# Power.net
KiCad netlist of a schematic drawn in Altium Designer
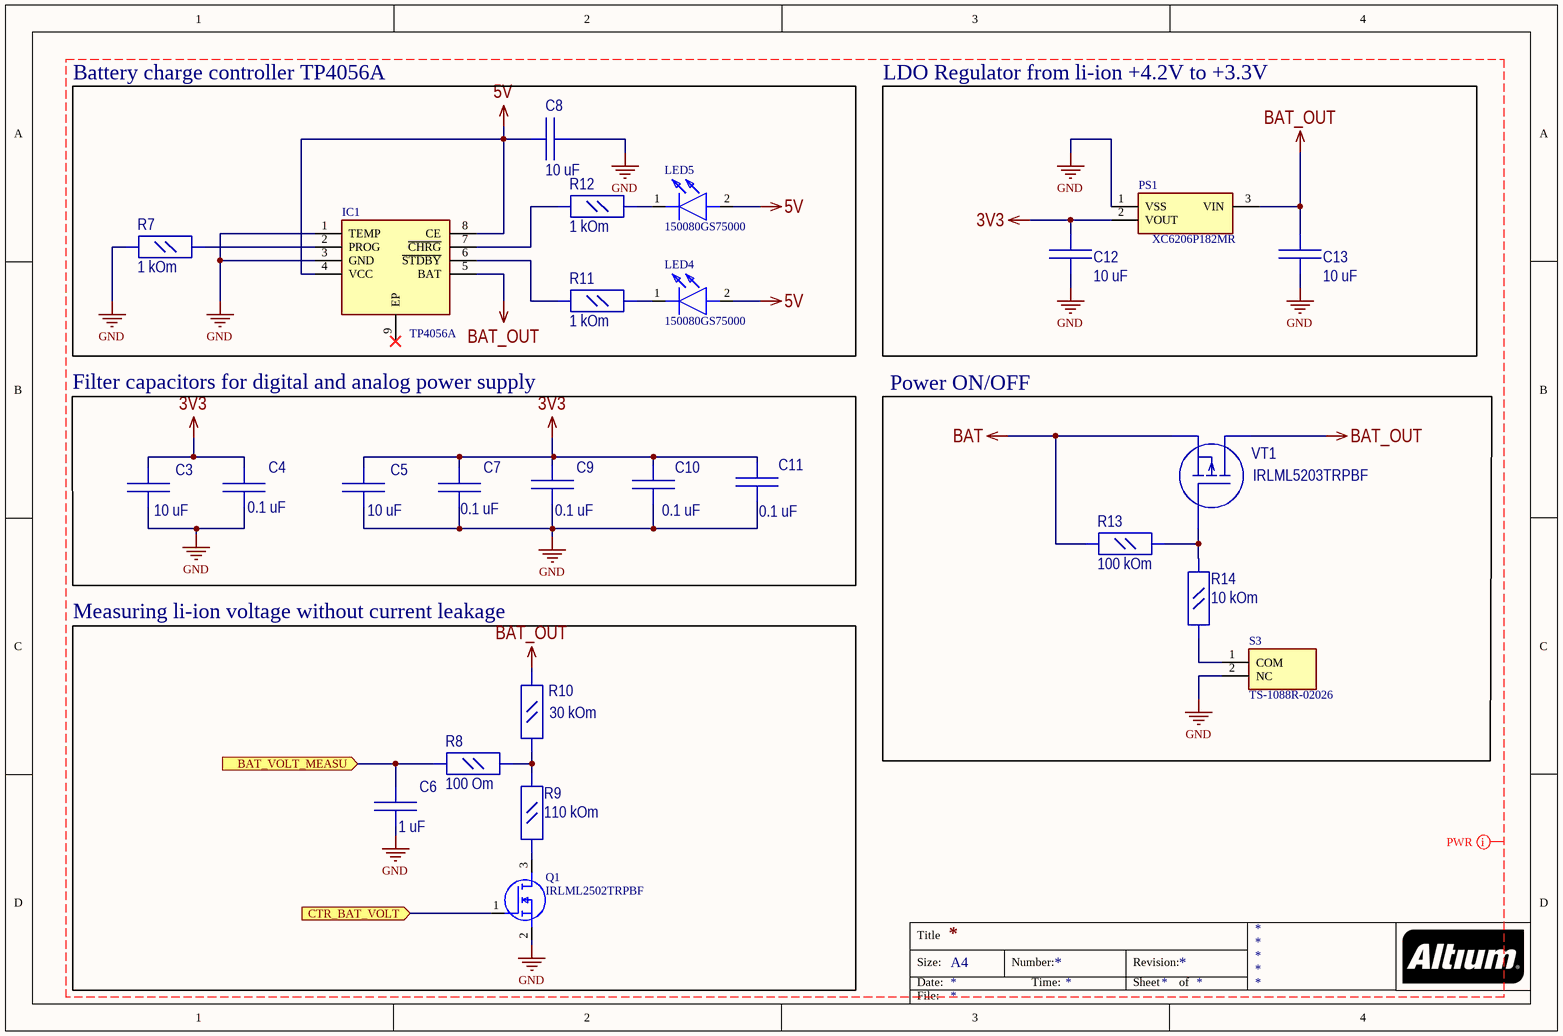
[diagram p0: Power.SchDoc]

(export (version "E")
  (design (tool "Eeschema 10.0.6"))
  (components
    (comp (ref "C3") (value "10 uF") (footprint "C_0805") (libsource (lib "2.Capasitors") (part "C_0805")))
    (comp (ref "C4") (value "0.1 uF") (footprint "C_0805") (libsource (lib "2.Capasitors") (part "C_0805")))
    (comp (ref "C5") (value "10 uF") (footprint "C_0805") (libsource (lib "2.Capasitors") (part "C_0805")))
    (comp (ref "C6") (value "1 uF") (footprint "C_0805") (libsource (lib "2.Capasitors") (part "C_0805")))
    (comp (ref "C7") (value "0.1 uF") (footprint "C_0805") (libsource (lib "2.Capasitors") (part "C_0805")))
    (comp (ref "C8") (value "10 uF") (footprint "C_0805") (libsource (lib "2.Capasitors") (part "C_0805")))
    (comp (ref "C9") (value "0.1 uF") (footprint "C_0805") (libsource (lib "2.Capasitors") (part "C_0805")))
    (comp (ref "C10") (value "0.1 uF") (footprint "C_0805") (libsource (lib "2.Capasitors") (part "C_0805")))
    (comp (ref "C11") (value "0.1 uF") (footprint "C_0805") (libsource (lib "2.Capasitors") (part "C_0805")))
    (comp (ref "C12") (value "10 uF") (footprint "C_0805") (libsource (lib "2.Capasitors") (part "C_0805")))
    (comp (ref "C13") (value "10 uF") (footprint "C_0805") (libsource (lib "2.Capasitors") (part "C_0805")))
    (comp (ref "IC1")
      (value "TP4056A")
      (footprint "SamacSys:SOIC127P600X175-9N")
      (description "Integrated Circuit")
      (libsource (lib "*") (part "TP4056A"))
    )
    (comp (ref "LED4")
      (value "150080GS75000")
      (footprint "SamacSys:LEDM2012X80N")
      (description "LED")
      (fields (field (name "MOUSER PART NUMBER") "710-150080GS75000"))
      (libsource (lib "*") (part "150080GS75000"))
    )
    (comp (ref "LED5")
      (value "150080GS75000")
      (footprint "SamacSys:LEDM2012X80N")
      (description "LED")
      (fields (field (name "MOUSER PART NUMBER") "710-150080GS75000"))
      (libsource (lib "*") (part "150080GS75000"))
    )
    (comp (ref "PS1")
      (value "XC6206P182MR")
      (footprint "SamacSys:SOT95P280X130-3N")
      (description "Power Supply")
      (libsource (lib "*") (part "XC6206P182MR"))
    )
    (comp (ref "Q1")
      (value "IRLML2502TRPBF")
      (footprint "SamacSys:SOT95P237X112-3N")
      (description "MOSFET (N-Channel)")
      (fields (field (name "MOUSER PART NUMBER") "942-IRLML2502TRPBF"))
      (libsource (lib "*") (part "IRLML2502TRPBF"))
    )
    (comp (ref "R7") (value "1 kOm") (footprint "R_0805") (libsource (lib "1.Resistors") (part "R_0805")))
    (comp (ref "R8") (value "100 Om") (footprint "R_0805") (libsource (lib "1.Resistors") (part "R_0805")))
    (comp (ref "R9") (value "110 kOm") (footprint "R_0805") (libsource (lib "1.Resistors") (part "R_0805")))
    (comp (ref "R10") (value "30 kOm") (footprint "R_0805") (libsource (lib "1.Resistors") (part "R_0805")))
    (comp (ref "R11") (value "1 kOm") (footprint "R_0805") (libsource (lib "1.Resistors") (part "R_0805")))
    (comp (ref "R12") (value "1 kOm") (footprint "R_0805") (libsource (lib "1.Resistors") (part "R_0805")))
    (comp (ref "R13") (value "100 kOm") (footprint "R_0805") (libsource (lib "1.Resistors") (part "R_0805")))
    (comp (ref "R14") (value "10 kOm") (footprint "R_0805") (libsource (lib "1.Resistors") (part "R_0805")))
    (comp (ref "S3")
      (value "TS-1088R-02026")
      (footprint "SamacSys:TS1088R02026")
      (description "Switch")
      (libsource (lib "*") (part "TS-1088R-02026"))
    )
    (comp (ref "VT1")
      (value "IRLML5203TRPBF")
      (footprint "SOT23")
      (description "Транзистор, P-канал 30В 3A logic")
      (libsource (lib "5.Transistors") (part "IRLML5203TRPBF"))
    )
  )
  (nets
    (net (code "1") (name "/BAT_VOLT_MEASU") (class "Default")
      (node (ref "C6") (pin "2") (pinfunction "2_2") (pintype "passive"))
      (node (ref "R8") (pin "2") (pinfunction "2_2") (pintype "passive"))
    )
    (net (code "2") (name "/CTR_BAT_VOLT") (class "Default")
      (node (ref "Q1") (pin "1") (pinfunction "G_1") (pintype "passive"))
    )
    (net (code "3") (name "3V3") (class "Default")
      (node (ref "C10") (pin "2") (pinfunction "2_2") (pintype "passive"))
      (node (ref "C11") (pin "2") (pinfunction "2_2") (pintype "passive"))
      (node (ref "C12") (pin "1") (pinfunction "1_1") (pintype "passive"))
      (node (ref "C3") (pin "2") (pinfunction "2_2") (pintype "passive"))
      (node (ref "C4") (pin "2") (pinfunction "2_2") (pintype "passive"))
      (node (ref "C5") (pin "2") (pinfunction "2_2") (pintype "passive"))
      (node (ref "C7") (pin "2") (pinfunction "2_2") (pintype "passive"))
      (node (ref "C9") (pin "2") (pinfunction "2_2") (pintype "passive"))
      (node (ref "PS1") (pin "2") (pinfunction "VOUT_2") (pintype "passive"))
    )
    (net (code "4") (name "5V") (class "Default")
      (node (ref "C8") (pin "2") (pinfunction "2_2") (pintype "passive"))
      (node (ref "IC1") (pin "4") (pinfunction "VCC_4") (pintype "passive"))
      (node (ref "IC1") (pin "8") (pinfunction "CE_8") (pintype "passive"))
      (node (ref "LED4") (pin "2") (pinfunction "A_2") (pintype "passive"))
      (node (ref "LED5") (pin "2") (pinfunction "A_2") (pintype "passive"))
    )
    (net (code "5") (name "BAT") (class "Default")
      (node (ref "R13") (pin "2") (pinfunction "2_2") (pintype "passive"))
      (node (ref "VT1") (pin "2") (pinfunction "S_2") (pintype "passive"))
    )
    (net (code "6") (name "BAT_OUT") (class "Default")
      (node (ref "C13") (pin "1") (pinfunction "1_1") (pintype "passive"))
      (node (ref "IC1") (pin "5") (pinfunction "BAT_5") (pintype "passive"))
      (node (ref "PS1") (pin "3") (pinfunction "VIN_3") (pintype "passive"))
      (node (ref "R10") (pin "2") (pinfunction "2_2") (pintype "passive"))
      (node (ref "VT1") (pin "3") (pinfunction "D_3") (pintype "passive"))
    )
    (net (code "7") (name "GND") (class "Default")
      (node (ref "C10") (pin "1") (pinfunction "1_1") (pintype "passive"))
      (node (ref "C11") (pin "1") (pinfunction "1_1") (pintype "passive"))
      (node (ref "C12") (pin "2") (pinfunction "2_2") (pintype "passive"))
      (node (ref "C13") (pin "2") (pinfunction "2_2") (pintype "passive"))
      (node (ref "C3") (pin "1") (pinfunction "1_1") (pintype "passive"))
      (node (ref "C4") (pin "1") (pinfunction "1_1") (pintype "passive"))
      (node (ref "C5") (pin "1") (pinfunction "1_1") (pintype "passive"))
      (node (ref "C6") (pin "1") (pinfunction "1_1") (pintype "passive"))
      (node (ref "C7") (pin "1") (pinfunction "1_1") (pintype "passive"))
      (node (ref "C8") (pin "1") (pinfunction "1_1") (pintype "passive"))
      (node (ref "C9") (pin "1") (pinfunction "1_1") (pintype "passive"))
      (node (ref "IC1") (pin "1") (pinfunction "TEMP_1") (pintype "passive"))
      (node (ref "IC1") (pin "3") (pinfunction "GND_3") (pintype "passive"))
      (node (ref "PS1") (pin "1") (pinfunction "VSS_1") (pintype "passive"))
      (node (ref "Q1") (pin "2") (pinfunction "S_2") (pintype "passive"))
      (node (ref "R7") (pin "2") (pinfunction "2_2") (pintype "passive"))
      (node (ref "S3") (pin "2") (pinfunction "NC_2") (pintype "passive"))
    )
    (net (code "8") (name "Net-(IC1-PROG)") (class "Default")
      (node (ref "IC1") (pin "2") (pinfunction "PROG_2") (pintype "passive"))
      (node (ref "R7") (pin "1") (pinfunction "1_1") (pintype "passive"))
    )
    (net (code "9") (name "Net-(IC1-~{CHRG})") (class "Default")
      (node (ref "IC1") (pin "7") (pinfunction "~{CHRG}_7") (pintype "passive"))
      (node (ref "R12") (pin "2") (pinfunction "2_2") (pintype "passive"))
    )
    (net (code "10") (name "Net-(IC1-~{STDBY})") (class "Default")
      (node (ref "IC1") (pin "6") (pinfunction "~{STDBY}_6") (pintype "passive"))
      (node (ref "R11") (pin "2") (pinfunction "2_2") (pintype "passive"))
    )
    (net (code "11") (name "Net-(LED4-K)") (class "Default")
      (node (ref "LED4") (pin "1") (pinfunction "K_1") (pintype "passive"))
      (node (ref "R11") (pin "1") (pinfunction "1_1") (pintype "passive"))
    )
    (net (code "12") (name "Net-(LED5-K)") (class "Default")
      (node (ref "LED5") (pin "1") (pinfunction "K_1") (pintype "passive"))
      (node (ref "R12") (pin "1") (pinfunction "1_1") (pintype "passive"))
    )
    (net (code "13") (name "Net-(Q1-D)") (class "Default")
      (node (ref "Q1") (pin "3") (pinfunction "D_3") (pintype "passive"))
      (node (ref "R9") (pin "1") (pinfunction "1_1") (pintype "passive"))
    )
    (net (code "14") (name "Net-(R10-Pad1)") (class "Default")
      (node (ref "R10") (pin "1") (pinfunction "1_1") (pintype "passive"))
      (node (ref "R8") (pin "1") (pinfunction "1_1") (pintype "passive"))
      (node (ref "R9") (pin "2") (pinfunction "2_2") (pintype "passive"))
    )
    (net (code "15") (name "Net-(S3-COM)") (class "Default")
      (node (ref "R14") (pin "1") (pinfunction "1_1") (pintype "passive"))
      (node (ref "S3") (pin "1") (pinfunction "COM_1") (pintype "passive"))
    )
    (net (code "16") (name "Net-(VT1-G)") (class "Default")
      (node (ref "R13") (pin "1") (pinfunction "1_1") (pintype "passive"))
      (node (ref "R14") (pin "2") (pinfunction "2_2") (pintype "passive"))
      (node (ref "VT1") (pin "1") (pinfunction "G_1") (pintype "passive"))
    )
    (net (code "17") (name "unconnected-(IC1-EP-Pad9)") (class "Default")
      (node (ref "IC1") (pin "9") (pinfunction "EP_9") (pintype "passive+no_connect"))
    )
  )
)
